# ElemoW12S-01.net
KiCad netlist of a schematic drawn in Altium Designer
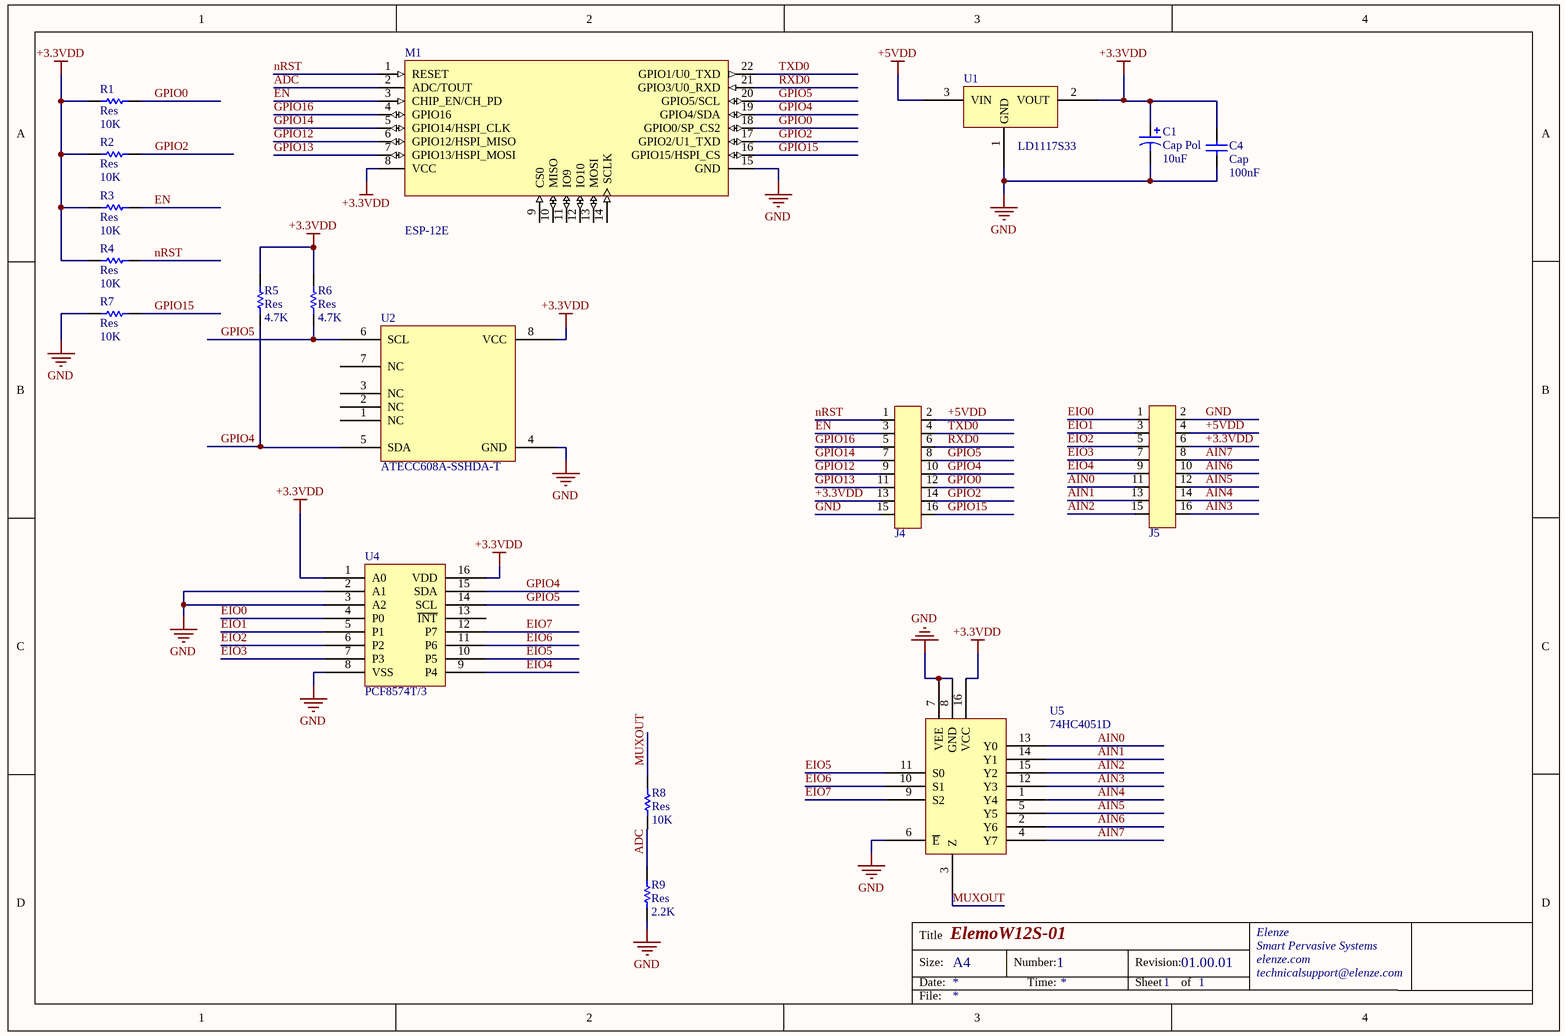
[diagram p0: ElemoW12S-01.SchDoc]

(export (version "E")
  (design (tool "Eeschema 10.0.6"))
  (components
    (comp (ref "C1")
      (value "Cap Pol")
      (footprint "1206P")
      (description "Polarized Capacitor (Axial)")
      (fields (field (name "ALTIUM_VALUE") "10uF") (field (name "PUBLISHER") "Altium Limited"))
      (libsource (lib "Elenze") (part "Cap Pol"))
    )
    (comp (ref "C4")
      (value "Cap")
      (footprint "0402")
      (description "Capacitor")
      (fields (field (name "ALTIUM_VALUE") "100nF") (field (name "PUBLISHER") "Altium Limited"))
      (libsource (lib "Elenze") (part "Cap"))
    )
    (comp (ref "J4")
      (value "2x8 PIN HEADER")
      (footprint "HDR_2X8_1.27_SMT")
      (libsource (lib "Elenze") (part "HEADER2x8"))
    )
    (comp (ref "J5")
      (value "2x8 PIN HEADER")
      (footprint "HDR_2X8_1.27_SMT")
      (libsource (lib "Elenze") (part "HEADER2x8"))
    )
    (comp (ref "M1")
      (value "ESP-12E")
      (footprint "ESP8266-12E")
      (description "ESP-12F WiFi module - developed by Ai-thinker Team")
      (libsource (lib "Elenze") (part "ESP-12E"))
    )
    (comp (ref "R1")
      (value "Res")
      (footprint "0402")
      (description "Resistor")
      (fields (field (name "ALTIUM_VALUE") "10K") (field (name "PUBLISHER") "Altium Limited"))
      (libsource (lib "Elenze") (part "Res"))
    )
    (comp (ref "R2")
      (value "Res")
      (footprint "0402")
      (description "Resistor")
      (fields (field (name "ALTIUM_VALUE") "10K") (field (name "PUBLISHER") "Altium Limited"))
      (libsource (lib "Elenze") (part "Res"))
    )
    (comp (ref "R3")
      (value "Res")
      (footprint "0402")
      (description "Resistor")
      (fields (field (name "ALTIUM_VALUE") "10K") (field (name "PUBLISHER") "Altium Limited"))
      (libsource (lib "Elenze") (part "Res"))
    )
    (comp (ref "R4")
      (value "Res")
      (footprint "0402")
      (description "Resistor")
      (fields (field (name "ALTIUM_VALUE") "10K") (field (name "PUBLISHER") "Altium Limited"))
      (libsource (lib "Elenze") (part "Res"))
    )
    (comp (ref "R5")
      (value "Res")
      (footprint "0402")
      (description "Resistor")
      (fields (field (name "ALTIUM_VALUE") "4.7K") (field (name "PUBLISHER") "Altium Limited"))
      (libsource (lib "Elenze") (part "Res"))
    )
    (comp (ref "R6")
      (value "Res")
      (footprint "0402")
      (description "Resistor")
      (fields (field (name "ALTIUM_VALUE") "4.7K") (field (name "PUBLISHER") "Altium Limited"))
      (libsource (lib "Elenze") (part "Res"))
    )
    (comp (ref "R7")
      (value "Res")
      (footprint "0402")
      (description "Resistor")
      (fields (field (name "ALTIUM_VALUE") "10K") (field (name "PUBLISHER") "Altium Limited"))
      (libsource (lib "Elenze") (part "Res"))
    )
    (comp (ref "R8")
      (value "Res")
      (footprint "0402")
      (description "Resistor")
      (fields (field (name "ALTIUM_VALUE") "10K") (field (name "PUBLISHER") "Altium Limited"))
      (libsource (lib "Elenze") (part "Res"))
    )
    (comp (ref "R9")
      (value "Res")
      (footprint "0402")
      (description "Resistor")
      (fields (field (name "ALTIUM_VALUE") "2.2K") (field (name "PUBLISHER") "Altium Limited"))
      (libsource (lib "Elenze") (part "Res"))
    )
    (comp (ref "U1")
      (value "LD1117S33")
      (footprint "SOT223_4")
      (description "IC REG LINEAR 3.3V 800MA")
      (fields (field (name "PART NUMBER") "LD1117S33CTR") (field (name "MANUFACTURER") "STMicroelectronics"))
      (libsource (lib "Elenze") (part "LD1117S33CTR"))
    )
    (comp (ref "U2")
      (value "ATECC608A-SSHDA-T")
      (footprint "SO_8N")
      (description "IC AUTHENTICATION CHIP 8SOIC")
      (fields (field (name "MF") "Microchip"))
      (libsource (lib "Elenze") (part "ATECC608A-SSHDA-T"))
    )
    (comp (ref "U4")
      (value "PCF8574T/3")
      (footprint "SO_16W")
      (description "I2C IO Expander")
      (libsource (lib "Elenze") (part "PCF8574T/3"))
    )
    (comp (ref "U5")
      (value "74HC4051D")
      (footprint "SO_16N")
      (description "CMOS ANALOG/DIGITAL MUX/DEMUX")
      (libsource (lib "Elenze") (part "74HC4051D"))
    )
  )
  (nets
    (net (code "1") (name "+3.3VDD") (class "Default")
      (node (ref "C1") (pin "1") (pinfunction "1_1") (pintype "passive"))
      (node (ref "C4") (pin "2") (pinfunction "2_2") (pintype "passive"))
      (node (ref "J4") (pin "13") (pinfunction "13_13") (pintype "passive"))
      (node (ref "J5") (pin "6") (pinfunction "6_6") (pintype "passive"))
      (node (ref "M1") (pin "8") (pinfunction "VCC_8") (pintype "power_in"))
      (node (ref "R1") (pin "1") (pinfunction "1_1") (pintype "passive"))
      (node (ref "R2") (pin "1") (pinfunction "1_1") (pintype "passive"))
      (node (ref "R3") (pin "1") (pinfunction "1_1") (pintype "passive"))
      (node (ref "R4") (pin "1") (pinfunction "1_1") (pintype "passive"))
      (node (ref "R5") (pin "2") (pinfunction "2_2") (pintype "passive"))
      (node (ref "R6") (pin "2") (pinfunction "2_2") (pintype "passive"))
      (node (ref "U1") (pin "2") (pinfunction "VOUT_2") (pintype "passive"))
      (node (ref "U2") (pin "8") (pinfunction "VCC_8") (pintype "passive"))
      (node (ref "U4") (pin "1") (pinfunction "A0_1") (pintype "passive"))
      (node (ref "U4") (pin "16") (pinfunction "VDD_16") (pintype "passive"))
      (node (ref "U5") (pin "16") (pinfunction "VCC_16") (pintype "passive"))
    )
    (net (code "2") (name "+5VDD") (class "Default")
      (node (ref "J4") (pin "2") (pinfunction "2_2") (pintype "passive"))
      (node (ref "J5") (pin "4") (pinfunction "4_4") (pintype "passive"))
      (node (ref "U1") (pin "3") (pinfunction "VIN_3") (pintype "passive"))
    )
    (net (code "3") (name "/ADC") (class "Default")
      (node (ref "M1") (pin "2") (pinfunction "ADC/TOUT_2") (pintype "passive"))
      (node (ref "R8") (pin "1") (pinfunction "1_1") (pintype "passive"))
      (node (ref "R9") (pin "2") (pinfunction "2_2") (pintype "passive"))
    )
    (net (code "4") (name "/AIN0") (class "Default")
      (node (ref "J5") (pin "11") (pinfunction "11_11") (pintype "passive"))
      (node (ref "U5") (pin "13") (pinfunction "Y0_13") (pintype "passive"))
    )
    (net (code "5") (name "/AIN1") (class "Default")
      (node (ref "J5") (pin "13") (pinfunction "13_13") (pintype "passive"))
      (node (ref "U5") (pin "14") (pinfunction "Y1_14") (pintype "passive"))
    )
    (net (code "6") (name "/AIN2") (class "Default")
      (node (ref "J5") (pin "15") (pinfunction "15_15") (pintype "passive"))
      (node (ref "U5") (pin "15") (pinfunction "Y2_15") (pintype "passive"))
    )
    (net (code "7") (name "/AIN3") (class "Default")
      (node (ref "J5") (pin "16") (pinfunction "16_16") (pintype "passive"))
      (node (ref "U5") (pin "12") (pinfunction "Y3_12") (pintype "passive"))
    )
    (net (code "8") (name "/AIN4") (class "Default")
      (node (ref "J5") (pin "14") (pinfunction "14_14") (pintype "passive"))
      (node (ref "U5") (pin "1") (pinfunction "Y4_1") (pintype "passive"))
    )
    (net (code "9") (name "/AIN5") (class "Default")
      (node (ref "J5") (pin "12") (pinfunction "12_12") (pintype "passive"))
      (node (ref "U5") (pin "5") (pinfunction "Y5_5") (pintype "passive"))
    )
    (net (code "10") (name "/AIN6") (class "Default")
      (node (ref "J5") (pin "10") (pinfunction "10_10") (pintype "passive"))
      (node (ref "U5") (pin "2") (pinfunction "Y6_2") (pintype "passive"))
    )
    (net (code "11") (name "/AIN7") (class "Default")
      (node (ref "J5") (pin "8") (pinfunction "8_8") (pintype "passive"))
      (node (ref "U5") (pin "4") (pinfunction "Y7_4") (pintype "passive"))
    )
    (net (code "12") (name "/EIO0") (class "Default")
      (node (ref "J5") (pin "1") (pinfunction "1_1") (pintype "passive"))
      (node (ref "U4") (pin "4") (pinfunction "P0_4") (pintype "passive"))
    )
    (net (code "13") (name "/EIO1") (class "Default")
      (node (ref "J5") (pin "3") (pinfunction "3_3") (pintype "passive"))
      (node (ref "U4") (pin "5") (pinfunction "P1_5") (pintype "passive"))
    )
    (net (code "14") (name "/EIO2") (class "Default")
      (node (ref "J5") (pin "5") (pinfunction "5_5") (pintype "passive"))
      (node (ref "U4") (pin "6") (pinfunction "P2_6") (pintype "passive"))
    )
    (net (code "15") (name "/EIO3") (class "Default")
      (node (ref "J5") (pin "7") (pinfunction "7_7") (pintype "passive"))
      (node (ref "U4") (pin "7") (pinfunction "P3_7") (pintype "passive"))
    )
    (net (code "16") (name "/EIO4") (class "Default")
      (node (ref "J5") (pin "9") (pinfunction "9_9") (pintype "passive"))
      (node (ref "U4") (pin "9") (pinfunction "P4_9") (pintype "passive"))
    )
    (net (code "17") (name "/EIO5") (class "Default")
      (node (ref "U4") (pin "10") (pinfunction "P5_10") (pintype "passive"))
      (node (ref "U5") (pin "11") (pinfunction "S0_11") (pintype "passive"))
    )
    (net (code "18") (name "/EIO6") (class "Default")
      (node (ref "U4") (pin "11") (pinfunction "P6_11") (pintype "passive"))
      (node (ref "U5") (pin "10") (pinfunction "S1_10") (pintype "passive"))
    )
    (net (code "19") (name "/EIO7") (class "Default")
      (node (ref "U4") (pin "12") (pinfunction "P7_12") (pintype "passive"))
      (node (ref "U5") (pin "9") (pinfunction "S2_9") (pintype "passive"))
    )
    (net (code "20") (name "/EN") (class "Default")
      (node (ref "J4") (pin "3") (pinfunction "3_3") (pintype "passive"))
      (node (ref "M1") (pin "3") (pinfunction "CHIP_EN/CH_PD_3") (pintype "input"))
      (node (ref "R3") (pin "2") (pinfunction "2_2") (pintype "passive"))
    )
    (net (code "21") (name "/GPIO0") (class "Default")
      (node (ref "J4") (pin "12") (pinfunction "12_12") (pintype "passive"))
      (node (ref "M1") (pin "18") (pinfunction "GPIO0/SP_CS2_18") (pintype "bidirectional"))
      (node (ref "R1") (pin "2") (pinfunction "2_2") (pintype "passive"))
    )
    (net (code "22") (name "/GPIO2") (class "Default")
      (node (ref "J4") (pin "14") (pinfunction "14_14") (pintype "passive"))
      (node (ref "M1") (pin "17") (pinfunction "GPIO2/U1_TXD_17") (pintype "bidirectional"))
      (node (ref "R2") (pin "2") (pinfunction "2_2") (pintype "passive"))
    )
    (net (code "23") (name "/GPIO4") (class "Default")
      (node (ref "J4") (pin "10") (pinfunction "10_10") (pintype "passive"))
      (node (ref "M1") (pin "19") (pinfunction "GPIO4/SDA_19") (pintype "bidirectional"))
      (node (ref "R5") (pin "1") (pinfunction "1_1") (pintype "passive"))
      (node (ref "U2") (pin "5") (pinfunction "SDA_5") (pintype "passive"))
      (node (ref "U4") (pin "15") (pinfunction "SDA_15") (pintype "passive"))
    )
    (net (code "24") (name "/GPIO5") (class "Default")
      (node (ref "J4") (pin "8") (pinfunction "8_8") (pintype "passive"))
      (node (ref "M1") (pin "20") (pinfunction "GPIO5/SCL_20") (pintype "bidirectional"))
      (node (ref "R6") (pin "1") (pinfunction "1_1") (pintype "passive"))
      (node (ref "U2") (pin "6") (pinfunction "SCL_6") (pintype "passive"))
      (node (ref "U4") (pin "14") (pinfunction "SCL_14") (pintype "passive"))
    )
    (net (code "25") (name "/GPIO12") (class "Default")
      (node (ref "J4") (pin "9") (pinfunction "9_9") (pintype "passive"))
      (node (ref "M1") (pin "6") (pinfunction "GPIO12/HSPI_MISO_6") (pintype "bidirectional"))
    )
    (net (code "26") (name "/GPIO13") (class "Default")
      (node (ref "J4") (pin "11") (pinfunction "11_11") (pintype "passive"))
      (node (ref "M1") (pin "7") (pinfunction "GPIO13/HSPI_MOSI_7") (pintype "bidirectional"))
    )
    (net (code "27") (name "/GPIO14") (class "Default")
      (node (ref "J4") (pin "7") (pinfunction "7_7") (pintype "passive"))
      (node (ref "M1") (pin "5") (pinfunction "GPIO14/HSPI_CLK_5") (pintype "bidirectional"))
    )
    (net (code "28") (name "/GPIO15") (class "Default")
      (node (ref "J4") (pin "16") (pinfunction "16_16") (pintype "passive"))
      (node (ref "M1") (pin "16") (pinfunction "GPIO15/HSPI_CS_16") (pintype "bidirectional"))
      (node (ref "R7") (pin "2") (pinfunction "2_2") (pintype "passive"))
    )
    (net (code "29") (name "/GPIO16") (class "Default")
      (node (ref "J4") (pin "5") (pinfunction "5_5") (pintype "passive"))
      (node (ref "M1") (pin "4") (pinfunction "GPIO16_4") (pintype "bidirectional"))
    )
    (net (code "30") (name "/MUXOUT") (class "Default")
      (node (ref "R8") (pin "2") (pinfunction "2_2") (pintype "passive"))
      (node (ref "U5") (pin "3") (pinfunction "Z_3") (pintype "passive"))
    )
    (net (code "31") (name "/RXD0") (class "Default")
      (node (ref "J4") (pin "6") (pinfunction "6_6") (pintype "passive"))
      (node (ref "M1") (pin "21") (pinfunction "GPIO3/U0_RXD_21") (pintype "input"))
    )
    (net (code "32") (name "/TXD0") (class "Default")
      (node (ref "J4") (pin "4") (pinfunction "4_4") (pintype "passive"))
      (node (ref "M1") (pin "22") (pinfunction "GPIO1/U0_TXD_22") (pintype "output"))
    )
    (net (code "33") (name "/nRST") (class "Default")
      (node (ref "J4") (pin "1") (pinfunction "1_1") (pintype "passive"))
      (node (ref "M1") (pin "1") (pinfunction "RESET_1") (pintype "input"))
      (node (ref "R4") (pin "2") (pinfunction "2_2") (pintype "passive"))
    )
    (net (code "34") (name "GND") (class "Default")
      (node (ref "C1") (pin "2") (pinfunction "2_2") (pintype "passive"))
      (node (ref "C4") (pin "1") (pinfunction "1_1") (pintype "passive"))
      (node (ref "J4") (pin "15") (pinfunction "15_15") (pintype "passive"))
      (node (ref "J5") (pin "2") (pinfunction "2_2") (pintype "passive"))
      (node (ref "M1") (pin "15") (pinfunction "GND_15") (pintype "power_in"))
      (node (ref "R7") (pin "1") (pinfunction "1_1") (pintype "passive"))
      (node (ref "R9") (pin "1") (pinfunction "1_1") (pintype "passive"))
      (node (ref "U1") (pin "1") (pinfunction "GND_1") (pintype "passive"))
      (node (ref "U2") (pin "4") (pinfunction "GND_4") (pintype "passive"))
      (node (ref "U4") (pin "2") (pinfunction "A1_2") (pintype "passive"))
      (node (ref "U4") (pin "3") (pinfunction "A2_3") (pintype "passive"))
      (node (ref "U4") (pin "8") (pinfunction "VSS_8") (pintype "passive"))
      (node (ref "U5") (pin "6") (pinfunction "~{E}_6") (pintype "passive"))
      (node (ref "U5") (pin "7") (pinfunction "VEE_7") (pintype "passive"))
      (node (ref "U5") (pin "8") (pinfunction "GND_8") (pintype "passive"))
    )
    (net (code "35") (name "unconnected-(M1-CS0-Pad9)") (class "Default")
      (node (ref "M1") (pin "9") (pinfunction "CS0_9") (pintype "input"))
    )
    (net (code "36") (name "unconnected-(M1-IO9-Pad11)") (class "Default")
      (node (ref "M1") (pin "11") (pinfunction "IO9_11") (pintype "bidirectional"))
    )
    (net (code "37") (name "unconnected-(M1-IO10-Pad12)") (class "Default")
      (node (ref "M1") (pin "12") (pinfunction "IO10_12") (pintype "bidirectional"))
    )
    (net (code "38") (name "unconnected-(M1-MISO-Pad10)") (class "Default")
      (node (ref "M1") (pin "10") (pinfunction "MISO_10") (pintype "bidirectional"))
    )
    (net (code "39") (name "unconnected-(M1-MOSI-Pad13)") (class "Default")
      (node (ref "M1") (pin "13") (pinfunction "MOSI_13") (pintype "bidirectional"))
    )
    (net (code "40") (name "unconnected-(M1-SCLK-Pad14)") (class "Default")
      (node (ref "M1") (pin "14") (pinfunction "SCLK_14") (pintype "input"))
    )
    (net (code "41") (name "unconnected-(U2-NC-Pad1)") (class "Default")
      (node (ref "U2") (pin "1") (pinfunction "NC_1") (pintype "passive"))
    )
    (net (code "42") (name "unconnected-(U2-NC-Pad2)") (class "Default")
      (node (ref "U2") (pin "2") (pinfunction "NC_2") (pintype "passive"))
    )
    (net (code "43") (name "unconnected-(U2-NC-Pad3)") (class "Default")
      (node (ref "U2") (pin "3") (pinfunction "NC_3") (pintype "passive"))
    )
    (net (code "44") (name "unconnected-(U2-NC-Pad7)") (class "Default")
      (node (ref "U2") (pin "7") (pinfunction "NC_7") (pintype "passive"))
    )
    (net (code "45") (name "unconnected-(U4-~{INT}-Pad13)") (class "Default")
      (node (ref "U4") (pin "13") (pinfunction "~{INT}_13") (pintype "passive"))
    )
  )
)
